# MCU052A_BOOSTXL-SHARP128.net
KiCad netlist of a schematic drawn in Altium Designer
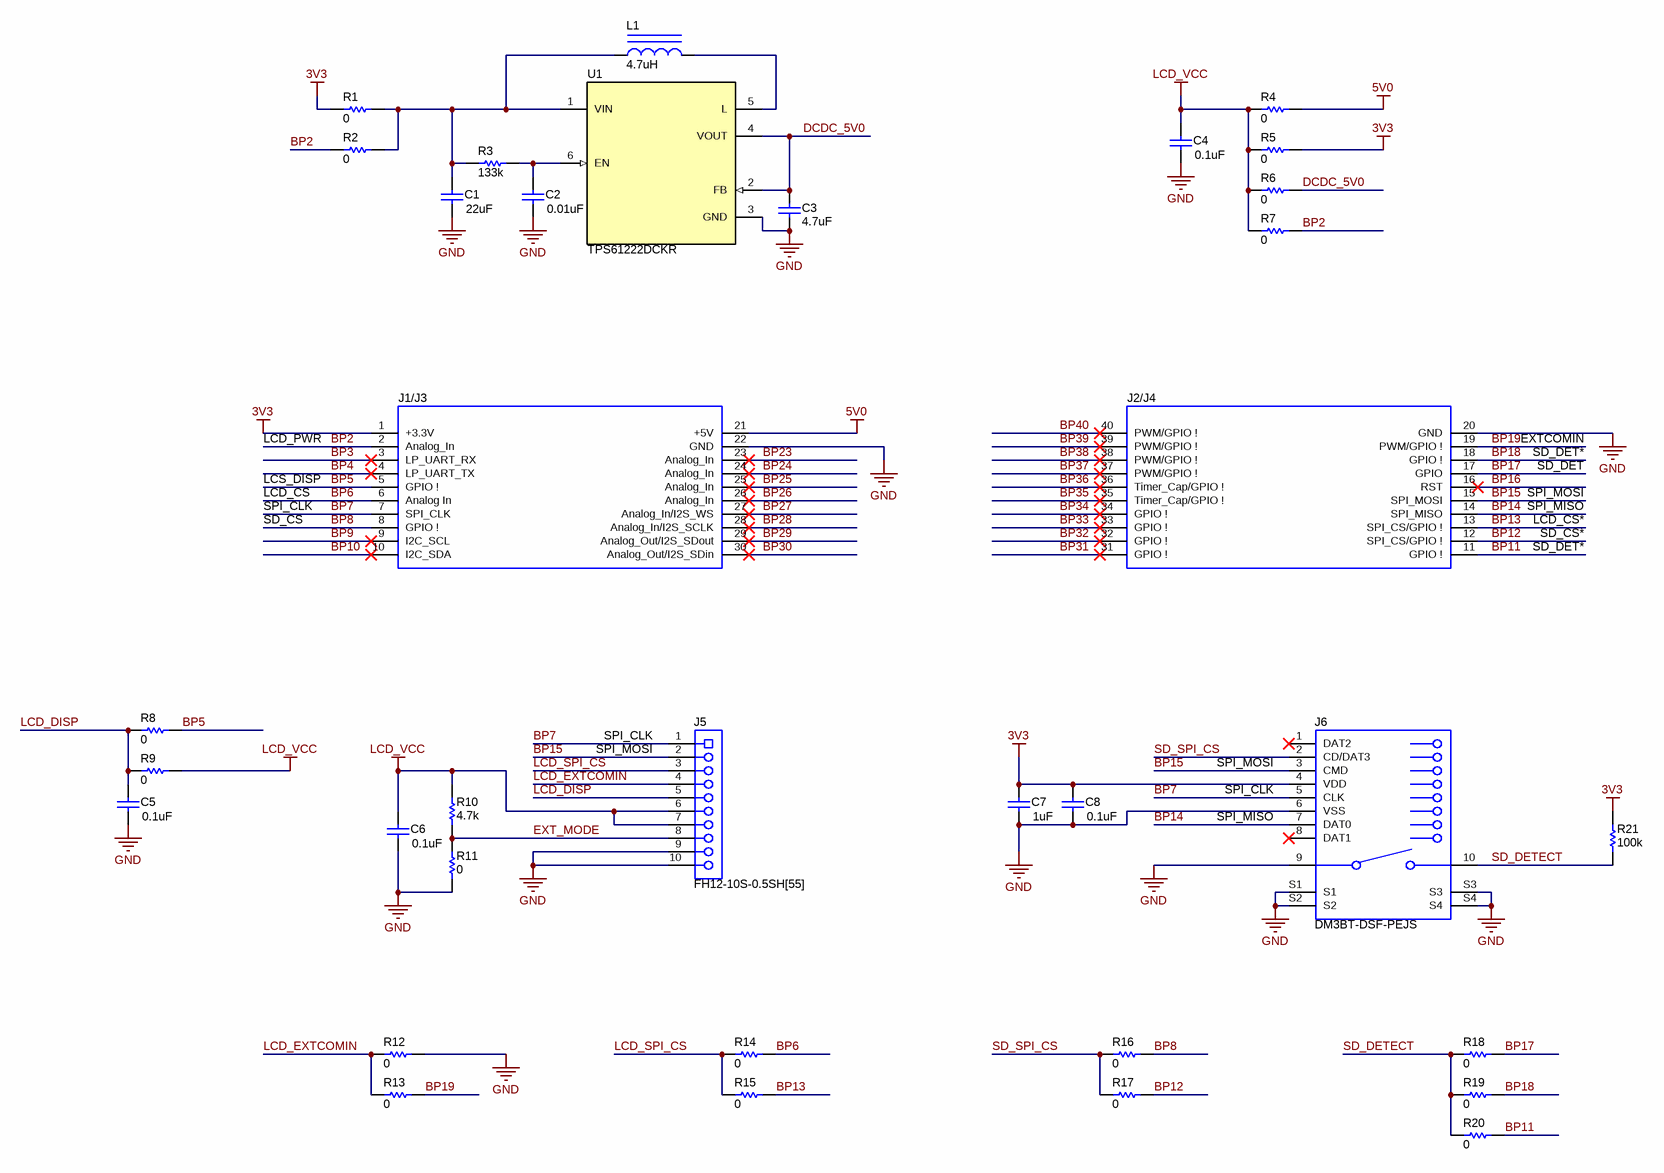
[diagram p0: MCU052A_BOOSTXL-SHARP128.SchDoc]

(export (version "E")
  (design (tool "Eeschema 10.0.6"))
  (components
    (comp (ref "C1")
      (value "GRM188R61A226ME15D")
      (footprint "0603")
      (description "CAP, CERM, 22 uF, 10 V, +/- 20%, X5R, 0603")
      (fields
        (field (name "MANUFACTURER") "MuRata")
        (field (name "VALUEDISPLAYED") "22uF")
        (field (name "PUBLISHER") "Texas Instruments")
      )
      (libsource (lib "Altium Vault - TI") (part "Capacitor"))
    )
    (comp (ref "C2")
      (value "GRM188R71E103KA01D")
      (footprint "0603")
      (description "CAP, CERM, 0.01 uF, 25 V, +/- 10%, X7R, 0603")
      (fields
        (field (name "MANUFACTURER") "MuRata")
        (field (name "VALUEDISPLAYED") "0.01uF")
        (field (name "PUBLISHER") "Texas Instruments")
      )
      (libsource (lib "Altium Vault - TI") (part "Capacitor"))
    )
    (comp (ref "C3")
      (value "GRM188C71A475KE11D")
      (footprint "0603")
      (description "CAP, CERM, 4.7 uF, 10 V, +/- 10%, X7S, 0603")
      (fields
        (field (name "MANUFACTURER") "MuRata")
        (field (name "VALUEDISPLAYED") "4.7uF")
        (field (name "PUBLISHER") "Texas Instruments")
      )
      (libsource (lib "Altium Vault - TI") (part "Capacitor"))
    )
    (comp (ref "C4")
      (value "GRM155R71A104KA01D")
      (footprint "0402")
      (description "CAP, CERM, 0.1 uF, 10 V, +/- 10%, X7R, 0402")
      (fields
        (field (name "MANUFACTURER") "MuRata")
        (field (name "VALUEDISPLAYED") "0.1uF")
        (field (name "PUBLISHER") "Texas Instruments")
      )
      (libsource (lib "Altium Vault - TI") (part "Capacitor"))
    )
    (comp (ref "C5")
      (value "GRM155R71A104KA01D")
      (footprint "0402")
      (description "CAP, CERM, 0.1 uF, 10 V, +/- 10%, X7R, 0402")
      (fields
        (field (name "MANUFACTURER") "MuRata")
        (field (name "VALUEDISPLAYED") "0.1uF")
        (field (name "PUBLISHER") "Texas Instruments")
      )
      (libsource (lib "Altium Vault - TI") (part "Capacitor"))
    )
    (comp (ref "C6")
      (value "GRM155R71A104KA01D")
      (footprint "0402")
      (description "CAP, CERM, 0.1 uF, 10 V, +/- 10%, X7R, 0402")
      (fields
        (field (name "MANUFACTURER") "MuRata")
        (field (name "VALUEDISPLAYED") "0.1uF")
        (field (name "PUBLISHER") "Texas Instruments")
      )
      (libsource (lib "Altium Vault - TI") (part "Capacitor"))
    )
    (comp (ref "C7")
      (value "GRM188R71C105KA12D")
      (footprint "0603")
      (description "CAP, CERM, 1 uF, 16 V, +/- 10%, X7R, 0603")
      (fields
        (field (name "MANUFACTURER") "MuRata")
        (field (name "VALUEDISPLAYED") "1uF")
        (field (name "PUBLISHER") "Texas Instruments")
      )
      (libsource (lib "Altium Vault - TI") (part "Capacitor"))
    )
    (comp (ref "C8")
      (value "GRM155R71A104KA01D")
      (footprint "0402")
      (description "CAP, CERM, 0.1 uF, 10 V, +/- 10%, X7R, 0402")
      (fields
        (field (name "MANUFACTURER") "MuRata")
        (field (name "VALUEDISPLAYED") "0.1uF")
        (field (name "PUBLISHER") "Texas Instruments")
      )
      (libsource (lib "Altium Vault - TI") (part "Capacitor"))
    )
    (comp (ref "J1/J3")
      (value "SSQ-110-03-T-D")
      (footprint "BoosterPack_40pin_J1J3")
      (description "Receptacle, 2.54mm, 10x2, Tin, TH")
      (fields (field (name "ALTERNATE PARTNUMBER") "CRD-081413-A-G") (field (name "MANUFACTURER") "Samtec"))
      (libsource (lib "Altium Vault - TI") (part "BoosterPack_40pin_J1J3"))
    )
    (comp (ref "J2/J4")
      (value "SSQ-110-03-T-D")
      (footprint "BoosterPack_40pin_J2J4")
      (description "Receptacle, 2.54mm, 10x2, Tin, TH")
      (fields (field (name "ALTERNATE PARTNUMBER") "CRD-081413-A-G") (field (name "MANUFACTURER") "Samtec"))
      (libsource (lib "Altium Vault - TI") (part "BoosterPack_40pin_J2J4"))
    )
    (comp (ref "J5")
      (value "FH12-10S-0.5SH[55]")
      (footprint "Hirose_FH12-10S-0_5SH[55]")
      (description "Connector, FPC 10 Pos. 9.1x2.0x5.6 mm")
      (fields
        (field (name "PARTNUMBER") "FH12-10S-0.5SH(55)")
        (field (name "MANUFACTURER") "Hirose Electric Co. Ltd.")
        (field (name "PUBLISHER") "Texas Instruments")
      )
      (libsource (lib "Altium Vault - TI") (part "Receptacle_10x1"))
    )
    (comp (ref "J6")
      (value "DM3BT-DSF-PEJS")
      (footprint "Hirose_DM3BT-DSF-PEJS")
      (description "Conncetor, micro SD, 8+2 Pos, R/A, SMT")
      (fields (field (name "MANUFACTURER") "Hirose Electric Co. Ltd."))
      (libsource (lib "Altium Vault - TI") (part "MicroSD_CD_4Shield"))
    )
    (comp (ref "L1")
      (value "EPL3015-472MLB")
      (footprint "EPL3015")
      (description "Inductor, Shielded, Ferrite, 4.7 uH, 1.2 A, 0.14 ohm, SMD")
      (fields
        (field (name "MANUFACTURER") "Coilcraft")
        (field (name "VALUEDISPLAYED") "4.7uH")
        (field (name "PUBLISHER") "Texas Instruments")
      )
      (libsource (lib "Altium Vault - TI") (part "Inductor_Iron"))
    )
    (comp (ref "R1")
      (value "CRCW06030000Z0EA")
      (footprint "0603")
      (description "RES, 0, 5%, 0.1 W, AEC-Q200 Grade 0, 0603")
      (fields (field (name "MANUFACTURER") "Vishay-Dale") (field (name "VALUEDISPLAYED") "0"))
      (libsource (lib "Altium Vault - TI") (part "Resistor"))
    )
    (comp (ref "R2")
      (value "CRCW06030000Z0EA")
      (footprint "0603")
      (description "RES, 0, 5%, 0.1 W, AEC-Q200 Grade 0, 0603")
      (fields (field (name "MANUFACTURER") "Vishay-Dale") (field (name "VALUEDISPLAYED") "0"))
      (libsource (lib "Altium Vault - TI") (part "Resistor"))
    )
    (comp (ref "R3")
      (value "CRCW0603133KFKEA")
      (footprint "0603")
      (description "RES, 133 k, 1%, 0.1 W, AEC-Q200 Grade 0, 0603")
      (fields (field (name "MANUFACTURER") "Vishay-Dale") (field (name "VALUEDISPLAYED") "133k"))
      (libsource (lib "Altium Vault - TI") (part "Resistor"))
    )
    (comp (ref "R4")
      (value "CRCW06030000Z0EA")
      (footprint "0603")
      (description "RES, 0, 5%, 0.1 W, AEC-Q200 Grade 0, 0603")
      (fields (field (name "MANUFACTURER") "Vishay-Dale") (field (name "VALUEDISPLAYED") "0"))
      (libsource (lib "Altium Vault - TI") (part "Resistor"))
    )
    (comp (ref "R5")
      (value "CRCW06030000Z0EA")
      (footprint "0603")
      (description "RES, 0, 5%, 0.1 W, AEC-Q200 Grade 0, 0603")
      (fields (field (name "MANUFACTURER") "Vishay-Dale") (field (name "VALUEDISPLAYED") "0"))
      (libsource (lib "Altium Vault - TI") (part "Resistor"))
    )
    (comp (ref "R6")
      (value "CRCW06030000Z0EA")
      (footprint "0603")
      (description "RES, 0, 5%, 0.1 W, AEC-Q200 Grade 0, 0603")
      (fields (field (name "MANUFACTURER") "Vishay-Dale") (field (name "VALUEDISPLAYED") "0"))
      (libsource (lib "Altium Vault - TI") (part "Resistor"))
    )
    (comp (ref "R7")
      (value "CRCW06030000Z0EA")
      (footprint "0603")
      (description "RES, 0, 5%, 0.1 W, AEC-Q200 Grade 0, 0603")
      (fields (field (name "MANUFACTURER") "Vishay-Dale") (field (name "VALUEDISPLAYED") "0"))
      (libsource (lib "Altium Vault - TI") (part "Resistor"))
    )
    (comp (ref "R8")
      (value "CRCW06030000Z0EA")
      (footprint "0603")
      (description "RES, 0, 5%, 0.1 W, AEC-Q200 Grade 0, 0603")
      (fields (field (name "MANUFACTURER") "Vishay-Dale") (field (name "VALUEDISPLAYED") "0"))
      (libsource (lib "Altium Vault - TI") (part "Resistor"))
    )
    (comp (ref "R9")
      (value "CRCW06030000Z0EA")
      (footprint "0603")
      (description "RES, 0, 5%, 0.1 W, AEC-Q200 Grade 0, 0603")
      (fields (field (name "MANUFACTURER") "Vishay-Dale") (field (name "VALUEDISPLAYED") "0"))
      (libsource (lib "Altium Vault - TI") (part "Resistor"))
    )
    (comp (ref "R10")
      (value "CRCW06034K70JNEA")
      (footprint "0603")
      (description "RES, 4.7 k, 5%, 0.1 W, AEC-Q200 Grade 0, 0603")
      (fields (field (name "MANUFACTURER") "Vishay-Dale") (field (name "VALUEDISPLAYED") "4.7k"))
      (libsource (lib "Altium Vault - TI") (part "Resistor"))
    )
    (comp (ref "R11")
      (value "CRCW06030000Z0EA")
      (footprint "0603")
      (description "RES, 0, 5%, 0.1 W, AEC-Q200 Grade 0, 0603")
      (fields (field (name "MANUFACTURER") "Vishay-Dale") (field (name "VALUEDISPLAYED") "0"))
      (libsource (lib "Altium Vault - TI") (part "Resistor"))
    )
    (comp (ref "R12")
      (value "CRCW06030000Z0EA")
      (footprint "0603")
      (description "RES, 0, 5%, 0.1 W, AEC-Q200 Grade 0, 0603")
      (fields (field (name "MANUFACTURER") "Vishay-Dale") (field (name "VALUEDISPLAYED") "0"))
      (libsource (lib "Altium Vault - TI") (part "Resistor"))
    )
    (comp (ref "R13")
      (value "CRCW06030000Z0EA")
      (footprint "0603")
      (description "RES, 0, 5%, 0.1 W, AEC-Q200 Grade 0, 0603")
      (fields (field (name "MANUFACTURER") "Vishay-Dale") (field (name "VALUEDISPLAYED") "0"))
      (libsource (lib "Altium Vault - TI") (part "Resistor"))
    )
    (comp (ref "R14")
      (value "CRCW06030000Z0EA")
      (footprint "0603")
      (description "RES, 0, 5%, 0.1 W, AEC-Q200 Grade 0, 0603")
      (fields (field (name "MANUFACTURER") "Vishay-Dale") (field (name "VALUEDISPLAYED") "0"))
      (libsource (lib "Altium Vault - TI") (part "Resistor"))
    )
    (comp (ref "R15")
      (value "CRCW06030000Z0EA")
      (footprint "0603")
      (description "RES, 0, 5%, 0.1 W, AEC-Q200 Grade 0, 0603")
      (fields (field (name "MANUFACTURER") "Vishay-Dale") (field (name "VALUEDISPLAYED") "0"))
      (libsource (lib "Altium Vault - TI") (part "Resistor"))
    )
    (comp (ref "R16")
      (value "CRCW06030000Z0EA")
      (footprint "0603")
      (description "RES, 0, 5%, 0.1 W, AEC-Q200 Grade 0, 0603")
      (fields (field (name "MANUFACTURER") "Vishay-Dale") (field (name "VALUEDISPLAYED") "0"))
      (libsource (lib "Altium Vault - TI") (part "Resistor"))
    )
    (comp (ref "R17")
      (value "CRCW06030000Z0EA")
      (footprint "0603")
      (description "RES, 0, 5%, 0.1 W, AEC-Q200 Grade 0, 0603")
      (fields (field (name "MANUFACTURER") "Vishay-Dale") (field (name "VALUEDISPLAYED") "0"))
      (libsource (lib "Altium Vault - TI") (part "Resistor"))
    )
    (comp (ref "R18")
      (value "CRCW06030000Z0EA")
      (footprint "0603")
      (description "RES, 0, 5%, 0.1 W, AEC-Q200 Grade 0, 0603")
      (fields (field (name "MANUFACTURER") "Vishay-Dale") (field (name "VALUEDISPLAYED") "0"))
      (libsource (lib "Altium Vault - TI") (part "Resistor"))
    )
    (comp (ref "R19")
      (value "CRCW06030000Z0EA")
      (footprint "0603")
      (description "RES, 0, 5%, 0.1 W, AEC-Q200 Grade 0, 0603")
      (fields (field (name "MANUFACTURER") "Vishay-Dale") (field (name "VALUEDISPLAYED") "0"))
      (libsource (lib "Altium Vault - TI") (part "Resistor"))
    )
    (comp (ref "R20")
      (value "CRCW06030000Z0EA")
      (footprint "0603")
      (description "RES, 0, 5%, 0.1 W, AEC-Q200 Grade 0, 0603")
      (fields (field (name "MANUFACTURER") "Vishay-Dale") (field (name "VALUEDISPLAYED") "0"))
      (libsource (lib "Altium Vault - TI") (part "Resistor"))
    )
    (comp (ref "R21")
      (value "CRCW0603100KFKEA")
      (footprint "0603")
      (description "RES, 100 k, 1%, 0.1 W, AEC-Q200 Grade 0, 0603")
      (fields (field (name "MANUFACTURER") "Vishay-Dale") (field (name "VALUEDISPLAYED") "100k"))
      (libsource (lib "Altium Vault - TI") (part "CMP-0021990-4"))
    )
    (comp (ref "U1")
      (value "TPS61222DCKR")
      (footprint "DCK0006A_N")
      (description "Tiny Low Input Voltage Boost Converter, DCK0006A (SOT-SC70-6)")
      (fields
        (field (name "ALTERNATE PARTNUMBER") "TPS61222DCKT")
        (field (name "MANUFACTURER") "Texas Instruments")
        (field (name "PARTNUMBER") "TPS61222DCKR")
      )
      (libsource (lib "Altium Vault - TI") (part "TPS6122x"))
    )
  )
  (nets
    (net (code "1") (name "/BP2") (class "Default")
      (node (ref "J1/J3") (pin "2") (pinfunction "Analog_In_2") (pintype "passive"))
      (node (ref "R2") (pin "1") (pinfunction "1_1") (pintype "passive"))
      (node (ref "R7") (pin "2") (pinfunction "2_2") (pintype "passive"))
    )
    (net (code "2") (name "/BP3") (class "Default")
      (node (ref "J1/J3") (pin "3") (pinfunction "LP_UART_RX_3") (pintype "passive+no_connect"))
    )
    (net (code "3") (name "/BP4") (class "Default")
      (node (ref "J1/J3") (pin "4") (pinfunction "LP_UART_TX_4") (pintype "passive+no_connect"))
    )
    (net (code "4") (name "/BP5") (class "Default")
      (node (ref "J1/J3") (pin "5") (pinfunction "GPIO_!_5") (pintype "passive"))
      (node (ref "R8") (pin "2") (pinfunction "2_2") (pintype "passive"))
    )
    (net (code "5") (name "/BP6") (class "Default")
      (node (ref "J1/J3") (pin "6") (pinfunction "Analog_In_6") (pintype "passive"))
      (node (ref "R14") (pin "2") (pinfunction "2_2") (pintype "passive"))
    )
    (net (code "6") (name "/BP7") (class "Default")
      (node (ref "J1/J3") (pin "7") (pinfunction "SPI_CLK_7") (pintype "passive"))
      (node (ref "J5") (pin "1") (pinfunction "1_1") (pintype "passive"))
      (node (ref "J6") (pin "5") (pinfunction "CLK_5") (pintype "passive"))
    )
    (net (code "7") (name "/BP8") (class "Default")
      (node (ref "J1/J3") (pin "8") (pinfunction "GPIO_!_8") (pintype "passive"))
      (node (ref "R16") (pin "2") (pinfunction "2_2") (pintype "passive"))
    )
    (net (code "8") (name "/BP9") (class "Default")
      (node (ref "J1/J3") (pin "9") (pinfunction "I2C_SCL_9") (pintype "passive+no_connect"))
    )
    (net (code "9") (name "/BP10") (class "Default")
      (node (ref "J1/J3") (pin "10") (pinfunction "I2C_SDA_10") (pintype "passive+no_connect"))
    )
    (net (code "10") (name "/BP11") (class "Default")
      (node (ref "J2/J4") (pin "11") (pinfunction "GPIO_!_11") (pintype "passive"))
      (node (ref "R20") (pin "2") (pinfunction "2_2") (pintype "passive"))
    )
    (net (code "11") (name "/BP12") (class "Default")
      (node (ref "J2/J4") (pin "12") (pinfunction "SPI_CS/GPIO_!_12") (pintype "passive"))
      (node (ref "R17") (pin "2") (pinfunction "2_2") (pintype "passive"))
    )
    (net (code "12") (name "/BP13") (class "Default")
      (node (ref "J2/J4") (pin "13") (pinfunction "SPI_CS/GPIO_!_13") (pintype "passive"))
      (node (ref "R15") (pin "2") (pinfunction "2_2") (pintype "passive"))
    )
    (net (code "13") (name "/BP14") (class "Default")
      (node (ref "J2/J4") (pin "14") (pinfunction "SPI_MISO_14") (pintype "passive"))
      (node (ref "J6") (pin "7") (pinfunction "DAT0_7") (pintype "passive"))
    )
    (net (code "14") (name "/BP15") (class "Default")
      (node (ref "J2/J4") (pin "15") (pinfunction "SPI_MOSI_15") (pintype "passive"))
      (node (ref "J5") (pin "2") (pinfunction "2_2") (pintype "passive"))
      (node (ref "J6") (pin "3") (pinfunction "CMD_3") (pintype "passive"))
    )
    (net (code "15") (name "/BP16") (class "Default")
      (node (ref "J2/J4") (pin "16") (pinfunction "RST_16") (pintype "passive+no_connect"))
    )
    (net (code "16") (name "/BP17") (class "Default")
      (node (ref "J2/J4") (pin "17") (pinfunction "GPIO_17") (pintype "passive"))
      (node (ref "R18") (pin "2") (pinfunction "2_2") (pintype "passive"))
    )
    (net (code "17") (name "/BP18") (class "Default")
      (node (ref "J2/J4") (pin "18") (pinfunction "GPIO_!_18") (pintype "passive"))
      (node (ref "R19") (pin "2") (pinfunction "2_2") (pintype "passive"))
    )
    (net (code "18") (name "/BP19") (class "Default")
      (node (ref "J2/J4") (pin "19") (pinfunction "PWM/GPIO_!_19") (pintype "passive"))
      (node (ref "R13") (pin "2") (pinfunction "2_2") (pintype "passive"))
    )
    (net (code "19") (name "/BP23") (class "Default")
      (node (ref "J1/J3") (pin "23") (pinfunction "Analog_In_23") (pintype "passive+no_connect"))
    )
    (net (code "20") (name "/BP24") (class "Default")
      (node (ref "J1/J3") (pin "24") (pinfunction "Analog_In_24") (pintype "passive+no_connect"))
    )
    (net (code "21") (name "/BP25") (class "Default")
      (node (ref "J1/J3") (pin "25") (pinfunction "Analog_In_25") (pintype "passive+no_connect"))
    )
    (net (code "22") (name "/BP26") (class "Default")
      (node (ref "J1/J3") (pin "26") (pinfunction "Analog_In_26") (pintype "passive+no_connect"))
    )
    (net (code "23") (name "/BP27") (class "Default")
      (node (ref "J1/J3") (pin "27") (pinfunction "Analog_In/I2S_WS_27") (pintype "passive+no_connect"))
    )
    (net (code "24") (name "/BP28") (class "Default")
      (node (ref "J1/J3") (pin "28") (pinfunction "Analog_In/I2S_SCLK_28") (pintype "passive+no_connect"))
    )
    (net (code "25") (name "/BP29") (class "Default")
      (node (ref "J1/J3") (pin "29") (pinfunction "Analog_Out/I2S_SDout_29") (pintype "passive+no_connect"))
    )
    (net (code "26") (name "/BP30") (class "Default")
      (node (ref "J1/J3") (pin "30") (pinfunction "Analog_Out/I2S_SDin_30") (pintype "passive+no_connect"))
    )
    (net (code "27") (name "/BP31") (class "Default")
      (node (ref "J2/J4") (pin "31") (pinfunction "GPIO_!_31") (pintype "passive+no_connect"))
    )
    (net (code "28") (name "/BP32") (class "Default")
      (node (ref "J2/J4") (pin "32") (pinfunction "GPIO_!_32") (pintype "passive+no_connect"))
    )
    (net (code "29") (name "/BP33") (class "Default")
      (node (ref "J2/J4") (pin "33") (pinfunction "GPIO_!_33") (pintype "passive+no_connect"))
    )
    (net (code "30") (name "/BP34") (class "Default")
      (node (ref "J2/J4") (pin "34") (pinfunction "GPIO_!_34") (pintype "passive+no_connect"))
    )
    (net (code "31") (name "/BP35") (class "Default")
      (node (ref "J2/J4") (pin "35") (pinfunction "Timer_Cap/GPIO_!_35") (pintype "passive+no_connect"))
    )
    (net (code "32") (name "/BP36") (class "Default")
      (node (ref "J2/J4") (pin "36") (pinfunction "Timer_Cap/GPIO_!_36") (pintype "passive+no_connect"))
    )
    (net (code "33") (name "/BP37") (class "Default")
      (node (ref "J2/J4") (pin "37") (pinfunction "PWM/GPIO_!_37") (pintype "passive+no_connect"))
    )
    (net (code "34") (name "/BP38") (class "Default")
      (node (ref "J2/J4") (pin "38") (pinfunction "PWM/GPIO_!_38") (pintype "passive+no_connect"))
    )
    (net (code "35") (name "/BP39") (class "Default")
      (node (ref "J2/J4") (pin "39") (pinfunction "PWM/GPIO_!_39") (pintype "passive+no_connect"))
    )
    (net (code "36") (name "/BP40") (class "Default")
      (node (ref "J2/J4") (pin "40") (pinfunction "PWM/GPIO_!_40") (pintype "passive+no_connect"))
    )
    (net (code "37") (name "/DCDC_5V0") (class "Default")
      (node (ref "C3") (pin "1") (pinfunction "1_1") (pintype "passive"))
      (node (ref "R6") (pin "2") (pinfunction "2_2") (pintype "passive"))
      (node (ref "U1") (pin "2") (pinfunction "FB_2") (pintype "input"))
      (node (ref "U1") (pin "4") (pinfunction "VOUT_4") (pintype "power_in"))
    )
    (net (code "38") (name "/EXT_MODE") (class "Default")
      (node (ref "J5") (pin "8") (pinfunction "8_8") (pintype "passive"))
      (node (ref "R10") (pin "1") (pinfunction "1_1") (pintype "passive"))
      (node (ref "R11") (pin "2") (pinfunction "2_2") (pintype "passive"))
    )
    (net (code "39") (name "/LCD_DISP") (class "Default")
      (node (ref "C5") (pin "1") (pinfunction "1_1") (pintype "passive"))
      (node (ref "J5") (pin "5") (pinfunction "5_5") (pintype "passive"))
      (node (ref "R8") (pin "1") (pinfunction "1_1") (pintype "passive"))
      (node (ref "R9") (pin "1") (pinfunction "1_1") (pintype "passive"))
    )
    (net (code "40") (name "/LCD_EXTCOMIN") (class "Default")
      (node (ref "J5") (pin "4") (pinfunction "4_4") (pintype "passive"))
      (node (ref "R12") (pin "1") (pinfunction "1_1") (pintype "passive"))
      (node (ref "R13") (pin "1") (pinfunction "1_1") (pintype "passive"))
    )
    (net (code "41") (name "/LCD_SPI_CS") (class "Default")
      (node (ref "J5") (pin "3") (pinfunction "3_3") (pintype "passive"))
      (node (ref "R14") (pin "1") (pinfunction "1_1") (pintype "passive"))
      (node (ref "R15") (pin "1") (pinfunction "1_1") (pintype "passive"))
    )
    (net (code "42") (name "/SD_DETECT") (class "Default")
      (node (ref "J6") (pin "10") (pinfunction "B_10") (pintype "passive"))
      (node (ref "R18") (pin "1") (pinfunction "1_1") (pintype "passive"))
      (node (ref "R19") (pin "1") (pinfunction "1_1") (pintype "passive"))
      (node (ref "R20") (pin "1") (pinfunction "1_1") (pintype "passive"))
      (node (ref "R21") (pin "1") (pinfunction "1_1") (pintype "passive"))
    )
    (net (code "43") (name "/SD_SPI_CS") (class "Default")
      (node (ref "J6") (pin "2") (pinfunction "CD/DAT3_2") (pintype "passive"))
      (node (ref "R16") (pin "1") (pinfunction "1_1") (pintype "passive"))
      (node (ref "R17") (pin "1") (pinfunction "1_1") (pintype "passive"))
    )
    (net (code "44") (name "3V3") (class "Default")
      (node (ref "C7") (pin "1") (pinfunction "1_1") (pintype "passive"))
      (node (ref "C8") (pin "1") (pinfunction "1_1") (pintype "passive"))
      (node (ref "J1/J3") (pin "1") (pinfunction "+3.3V_1") (pintype "power_in"))
      (node (ref "J6") (pin "4") (pinfunction "VDD_4") (pintype "passive"))
      (node (ref "R1") (pin "1") (pinfunction "1_1") (pintype "passive"))
      (node (ref "R21") (pin "2") (pinfunction "2_2") (pintype "passive"))
      (node (ref "R5") (pin "2") (pinfunction "2_2") (pintype "passive"))
    )
    (net (code "45") (name "5V0") (class "Default")
      (node (ref "J1/J3") (pin "21") (pinfunction "+5V_21") (pintype "power_in"))
      (node (ref "R4") (pin "2") (pinfunction "2_2") (pintype "passive"))
    )
    (net (code "46") (name "GND") (class "Default")
      (node (ref "C1") (pin "2") (pinfunction "2_2") (pintype "passive"))
      (node (ref "C2") (pin "2") (pinfunction "2_2") (pintype "passive"))
      (node (ref "C3") (pin "2") (pinfunction "2_2") (pintype "passive"))
      (node (ref "C4") (pin "2") (pinfunction "2_2") (pintype "passive"))
      (node (ref "C5") (pin "2") (pinfunction "2_2") (pintype "passive"))
      (node (ref "C6") (pin "2") (pinfunction "2_2") (pintype "passive"))
      (node (ref "C7") (pin "2") (pinfunction "2_2") (pintype "passive"))
      (node (ref "C8") (pin "2") (pinfunction "2_2") (pintype "passive"))
      (node (ref "J1/J3") (pin "22") (pinfunction "GND_22") (pintype "power_in"))
      (node (ref "J2/J4") (pin "20") (pinfunction "GND_20") (pintype "power_in"))
      (node (ref "J5") (pin "10") (pinfunction "10_10") (pintype "passive"))
      (node (ref "J5") (pin "9") (pinfunction "9_9") (pintype "passive"))
      (node (ref "J6") (pin "6") (pinfunction "VSS_6") (pintype "passive"))
      (node (ref "J6") (pin "9") (pinfunction "A_9") (pintype "passive"))
      (node (ref "J6") (pin "S1") (pinfunction "S1_S1") (pintype "passive"))
      (node (ref "J6") (pin "S2") (pinfunction "S2_S2") (pintype "passive"))
      (node (ref "J6") (pin "S3") (pinfunction "S3_S3") (pintype "passive"))
      (node (ref "J6") (pin "S4") (pinfunction "S4_S4") (pintype "passive"))
      (node (ref "R11") (pin "1") (pinfunction "1_1") (pintype "passive"))
      (node (ref "R12") (pin "2") (pinfunction "2_2") (pintype "passive"))
      (node (ref "U1") (pin "3") (pinfunction "GND_3") (pintype "power_in"))
    )
    (net (code "47") (name "LCD_VCC") (class "Default")
      (node (ref "C4") (pin "1") (pinfunction "1_1") (pintype "passive"))
      (node (ref "C6") (pin "1") (pinfunction "1_1") (pintype "passive"))
      (node (ref "J5") (pin "6") (pinfunction "6_6") (pintype "passive"))
      (node (ref "J5") (pin "7") (pinfunction "7_7") (pintype "passive"))
      (node (ref "R10") (pin "2") (pinfunction "2_2") (pintype "passive"))
      (node (ref "R4") (pin "1") (pinfunction "1_1") (pintype "passive"))
      (node (ref "R5") (pin "1") (pinfunction "1_1") (pintype "passive"))
      (node (ref "R6") (pin "1") (pinfunction "1_1") (pintype "passive"))
      (node (ref "R7") (pin "1") (pinfunction "1_1") (pintype "passive"))
      (node (ref "R9") (pin "2") (pinfunction "2_2") (pintype "passive"))
    )
    (net (code "48") (name "Net-(U1-EN)") (class "Default")
      (node (ref "C2") (pin "1") (pinfunction "1_1") (pintype "passive"))
      (node (ref "R3") (pin "2") (pinfunction "2_2") (pintype "passive"))
      (node (ref "U1") (pin "6") (pinfunction "EN_6") (pintype "input"))
    )
    (net (code "49") (name "Net-(U1-L)") (class "Default")
      (node (ref "L1") (pin "2") (pinfunction "2_2") (pintype "passive"))
      (node (ref "U1") (pin "5") (pinfunction "L_5") (pintype "passive"))
    )
    (net (code "50") (name "Net-(U1-VIN)") (class "Default")
      (node (ref "C1") (pin "1") (pinfunction "1_1") (pintype "passive"))
      (node (ref "L1") (pin "1") (pinfunction "1_1") (pintype "passive"))
      (node (ref "R1") (pin "2") (pinfunction "2_2") (pintype "passive"))
      (node (ref "R2") (pin "2") (pinfunction "2_2") (pintype "passive"))
      (node (ref "R3") (pin "1") (pinfunction "1_1") (pintype "passive"))
      (node (ref "U1") (pin "1") (pinfunction "VIN_1") (pintype "power_in"))
    )
    (net (code "51") (name "unconnected-(J6-DAT1-Pad8)") (class "Default")
      (node (ref "J6") (pin "8") (pinfunction "DAT1_8") (pintype "passive+no_connect"))
    )
    (net (code "52") (name "unconnected-(J6-DAT2-Pad1)") (class "Default")
      (node (ref "J6") (pin "1") (pinfunction "DAT2_1") (pintype "passive+no_connect"))
    )
  )
)
